# uven2-mk3-lid-switch-B.net
KiCad netlist of a schematic drawn in EasyEDA Pro
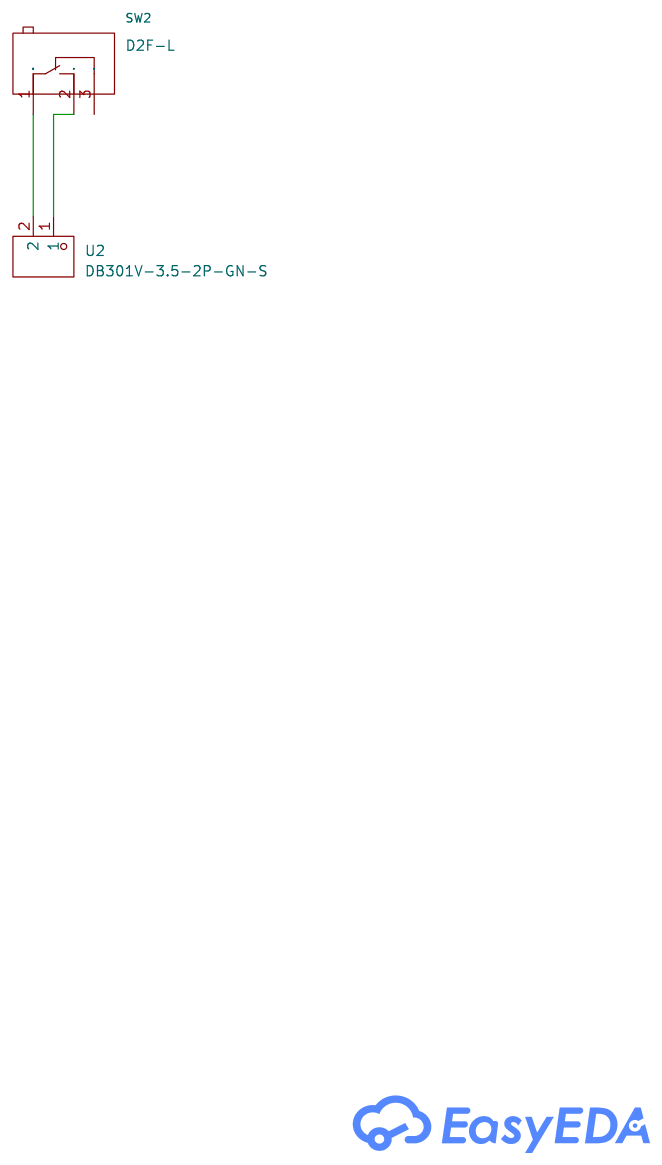
[diagram p0: schematic sheet]

(export (version "E")
  (design (tool "Eeschema 10.0.6"))
  (components
    (comp (ref "SW2")
      (value "D2F-L")
      (footprint "easyedapro:SW-TH_D2F-L")
      (fields (field (name "Manufacturer") "OMRON(欧姆龙)"))
      (libsource (lib "easyedapro") (part "D2F-L"))
    )
    (comp (ref "U2")
      (value "DB301V-3.5-2P-GN-S")
      (footprint "easyedapro:CONN-TH_DB301V-3.5-2P-GN")
      (fields (field (name "Manufacturer") "DORABO(地博电气)"))
      (libsource (lib "easyedapro") (part "DB301V-3.5-2P-GN"))
    )
  )
  (nets
    (net (code "1") (name "Net-(SW2-COM)") (class "Default")
      (node (ref "SW2") (pin "1") (pinfunction "COM_1") (pintype "input"))
      (node (ref "U2") (pin "2") (pinfunction "2_2") (pintype "unspecified"))
    )
    (net (code "2") (name "Net-(SW2-NO)") (class "Default")
      (node (ref "SW2") (pin "2") (pinfunction "NO_2") (pintype "input"))
      (node (ref "U2") (pin "1") (pinfunction "1_1") (pintype "unspecified"))
    )
    (net (code "3") (name "unconnected-(SW2-NC-Pad3)") (class "Default")
      (node (ref "SW2") (pin "3") (pinfunction "NC_3") (pintype "input"))
    )
  )
)
